# SimpleSwitchPirLightCO2.net
KiCad netlist of a schematic drawn in EAGLE
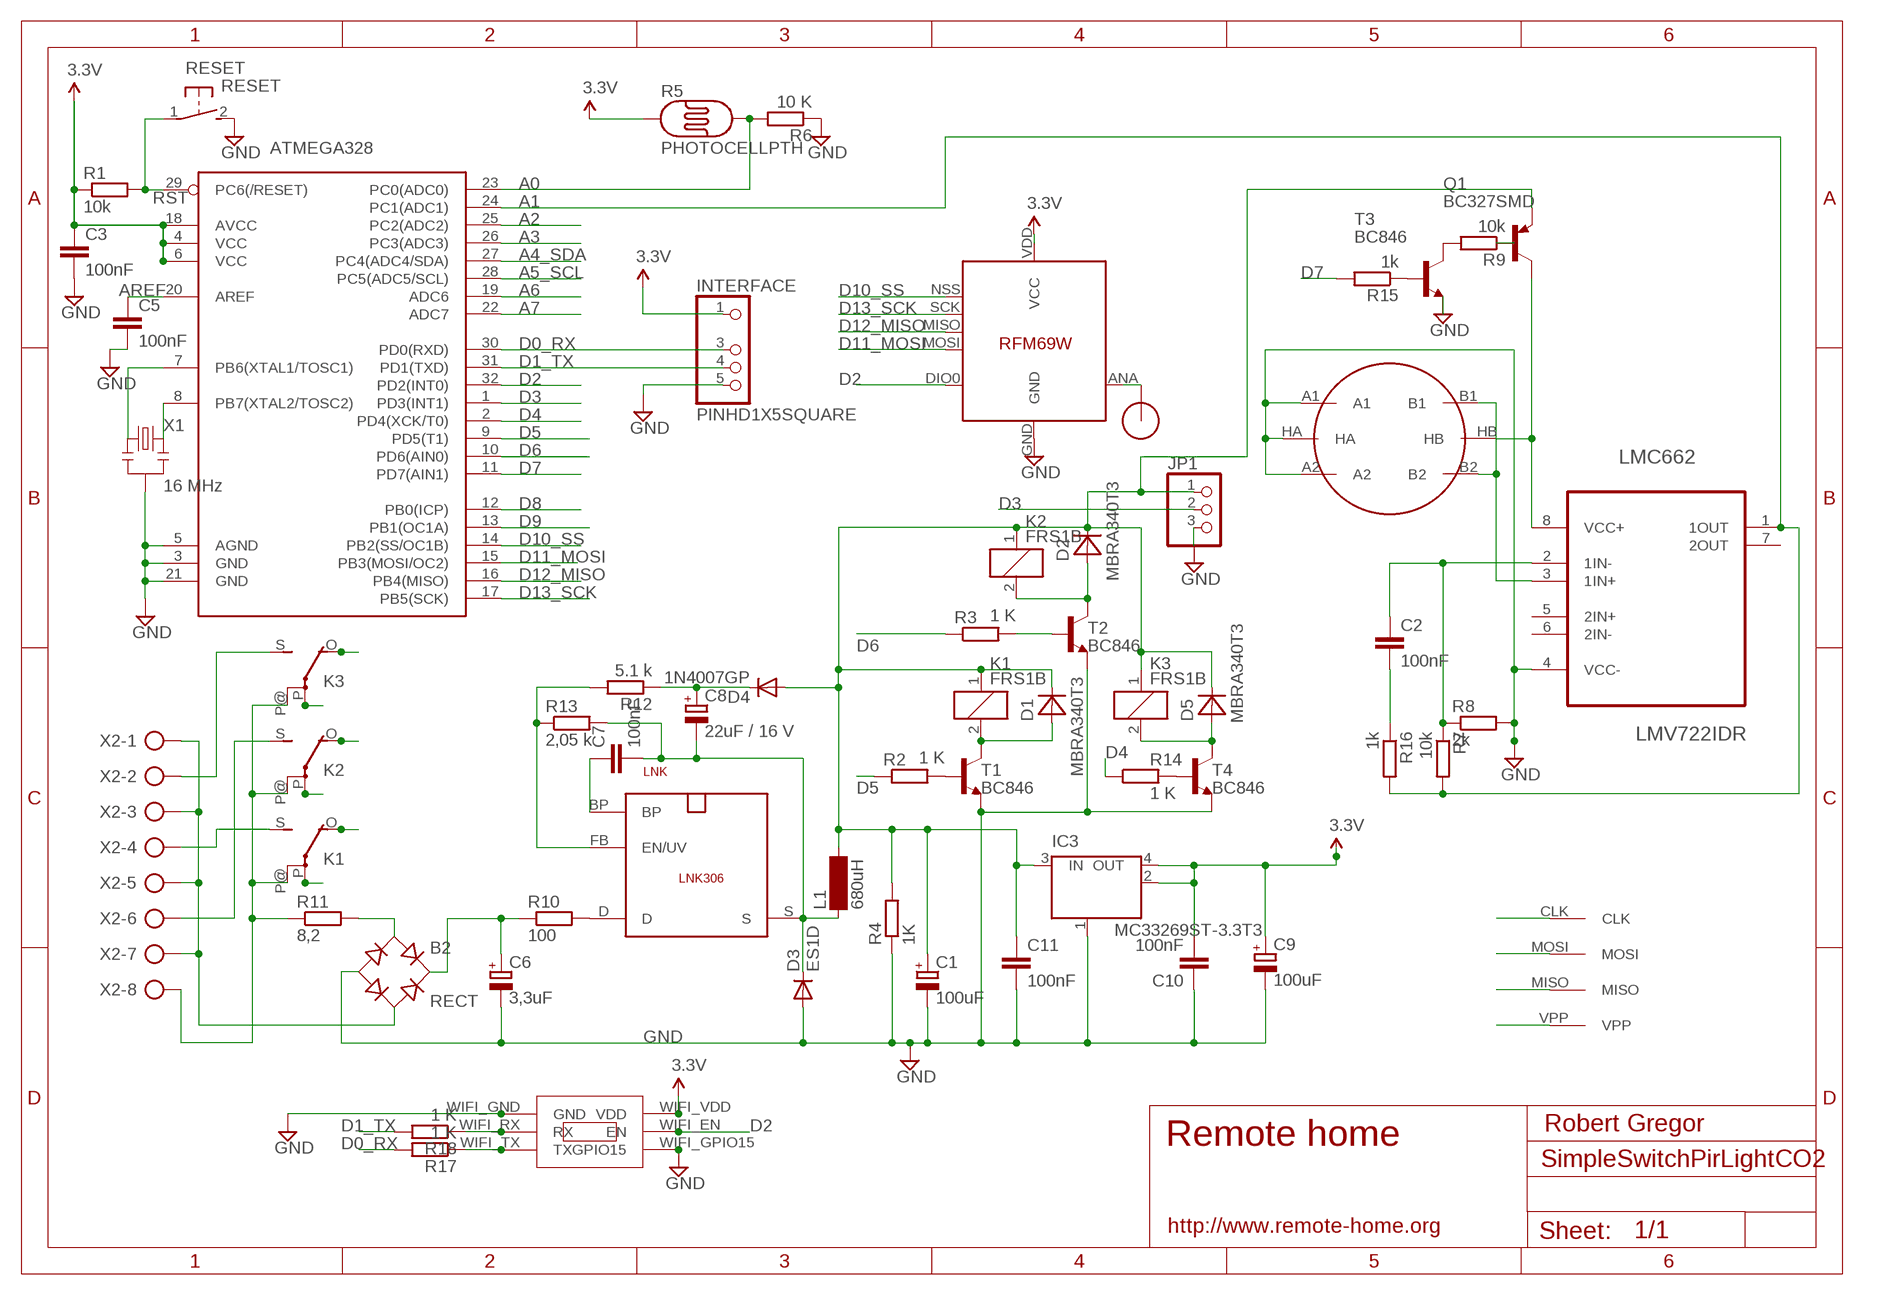
[diagram p0: schematic, sheet 1]

(export (version "E")
  (design (tool "Eeschema 10.0.6"))
  (components
    (comp (ref "ATMEGA328")
      (value "ATMega-328")
      (footprint "eagle-import:TQFP32-08")
      (libsource (lib "eagle-import") (part "ATMEGA168/328TQFP32"))
    )
    (comp (ref "B2")
      (value "RECT")
      (footprint "eagle-import:TO-269AA")
      (libsource (lib "eagle-import") (part "RECTIFIER-S40"))
    )
    (comp (ref "C1")
      (value "100uF")
      (footprint "eagle-import:SMC_B")
      (libsource (lib "eagle-import") (part "CPOL-EUSMCB"))
    )
    (comp (ref "C2")
      (value "100nF")
      (footprint "eagle-import:C2012")
      (libsource (lib "eagle-import") (part "C-EUC2012"))
    )
    (comp (ref "C3")
      (value "100nF")
      (footprint "eagle-import:C2012")
      (libsource (lib "eagle-import") (part "C-EUC2012"))
    )
    (comp (ref "C5")
      (value "100nF")
      (footprint "eagle-import:C2012")
      (libsource (lib "eagle-import") (part "C-EUC2012"))
    )
    (comp (ref "C6")
      (value "3,3uF")
      (footprint "eagle-import:E5-10,5")
      (libsource (lib "eagle-import") (part "CPOL-EUE5-10.5"))
    )
    (comp (ref "C7")
      (value "100nF")
      (footprint "eagle-import:C2012")
      (libsource (lib "eagle-import") (part "C-EUC2012"))
    )
    (comp (ref "C8")
      (value "22uF / 16 V")
      (footprint "eagle-import:SMC_C")
      (libsource (lib "eagle-import") (part "CPOL-EUSMCC"))
    )
    (comp (ref "C9")
      (value "100uF")
      (footprint "eagle-import:SMC_B")
      (libsource (lib "eagle-import") (part "CPOL-EUSMCB"))
    )
    (comp (ref "C10")
      (value "100nF")
      (footprint "eagle-import:C2012")
      (libsource (lib "eagle-import") (part "C-EUC2012"))
    )
    (comp (ref "C11")
      (value "100nF")
      (footprint "eagle-import:C2012")
      (libsource (lib "eagle-import") (part "C-EUC2012"))
    )
    (comp (ref "D1")
      (value "MBRA340T3")
      (footprint "eagle-import:SMA")
      (libsource (lib "eagle-import") (part "MBRA340T3"))
    )
    (comp (ref "D2")
      (value "MBRA340T3")
      (footprint "eagle-import:SMA")
      (libsource (lib "eagle-import") (part "MBRA340T3"))
    )
    (comp (ref "D3")
      (value "ES1D")
      (footprint "eagle-import:DO214AC")
      (libsource (lib "eagle-import") (part "DIODE-DO214AC"))
    )
    (comp (ref "D4")
      (value "1N4007GP")
      (footprint "eagle-import:DO214AA")
      (libsource (lib "eagle-import") (part "DIODE-DO214AA"))
    )
    (comp (ref "D5")
      (value "MBRA340T3")
      (footprint "eagle-import:SMA")
      (libsource (lib "eagle-import") (part "MBRA340T3"))
    )
    (comp (ref "IC3")
      (value "MC33269ST-3.3T3")
      (footprint "eagle-import:SOT223")
      (libsource (lib "eagle-import") (part "MC33269ST-3.3T3"))
    )
    (comp (ref "INTERFACE")
      (value "PINHD1X5SQUARE")
      (footprint "eagle-import:PINHD1X05-SQUARE")
      (libsource (lib "eagle-import") (part "PINHD1X5SQUARE"))
    )
    (comp (ref "JP1")
      (value "PINHD-1X03_2.54-S")
      (footprint "eagle-import:1X03-S")
      (libsource (lib "eagle-import") (part "PINHD-1X03_2.54-S"))
    )
    (comp (ref "K1")
      (value "FRS1B")
      (footprint "eagle-import:FRS1B")
      (libsource (lib "eagle-import") (part "FRS1B"))
    )
    (comp (ref "K2")
      (value "FRS1B")
      (footprint "eagle-import:FRS1B")
      (libsource (lib "eagle-import") (part "FRS1B"))
    )
    (comp (ref "K3")
      (value "FRS1B")
      (footprint "eagle-import:FRS1B")
      (libsource (lib "eagle-import") (part "FRS1B"))
    )
    (comp (ref "L1")
      (value "680uH")
      (footprint "eagle-import:BS11")
      (libsource (lib "eagle-import") (part "BS11"))
    )
    (comp (ref "LMC662")
      (value "LMV722IDR")
      (footprint "eagle-import:SOIC127P600X175-8N")
      (libsource (lib "eagle-import") (part "LMV722IDR"))
    )
    (comp (ref "LNK")
      (value "LNK306")
      (footprint "eagle-import:SO-8C")
      (libsource (lib "eagle-import") (part "SO-8C"))
    )
    (comp (ref "Q1")
      (value "BC327SMD")
      (footprint "eagle-import:SOT23-BEC")
      (libsource (lib "eagle-import") (part "BC327SMD"))
    )
    (comp (ref "R1")
      (value "10k")
      (footprint "eagle-import:R2012")
      (libsource (lib "eagle-import") (part "R-EU_R2012"))
    )
    (comp (ref "R2")
      (value "1 K")
      (footprint "eagle-import:M2012")
      (libsource (lib "eagle-import") (part "R-EU_M2012"))
    )
    (comp (ref "R3")
      (value "1 K")
      (footprint "eagle-import:M2012")
      (libsource (lib "eagle-import") (part "R-EU_M2012"))
    )
    (comp (ref "R4")
      (value "1K")
      (footprint "eagle-import:M2012")
      (libsource (lib "eagle-import") (part "R-EU_M2012"))
    )
    (comp (ref "R5")
      (value "PHOTOCELLPTH")
      (footprint "eagle-import:PHOTOCELL")
      (libsource (lib "eagle-import") (part "PHOTOCELLPTH"))
    )
    (comp (ref "R6")
      (value "10 K")
      (footprint "eagle-import:M2012")
      (libsource (lib "eagle-import") (part "R-EU_M2012"))
    )
    (comp (ref "R7")
      (value "10k")
      (footprint "eagle-import:R2012")
      (libsource (lib "eagle-import") (part "R-EU_R2012"))
    )
    (comp (ref "R8")
      (value "2k")
      (footprint "eagle-import:R2012")
      (libsource (lib "eagle-import") (part "R-EU_R2012"))
    )
    (comp (ref "R9")
      (value "10k")
      (footprint "eagle-import:R2012")
      (libsource (lib "eagle-import") (part "R-EU_R2012"))
    )
    (comp (ref "R10")
      (value "100")
      (footprint "eagle-import:R2512W")
      (libsource (lib "eagle-import") (part "R-EU_R2512W"))
    )
    (comp (ref "R11")
      (value "8,2")
      (footprint "eagle-import:0411_12")
      (libsource (lib "eagle-import") (part "R-EU_0411/12"))
    )
    (comp (ref "R12")
      (value "5.1 k")
      (footprint "eagle-import:M2012")
      (libsource (lib "eagle-import") (part "R-EU_M2012"))
    )
    (comp (ref "R13")
      (value "2,05 k")
      (footprint "eagle-import:M2012")
      (libsource (lib "eagle-import") (part "R-EU_M2012"))
    )
    (comp (ref "R14")
      (value "1 K")
      (footprint "eagle-import:M2012")
      (libsource (lib "eagle-import") (part "R-EU_M2012"))
    )
    (comp (ref "R15")
      (value "1k")
      (footprint "eagle-import:R2012")
      (libsource (lib "eagle-import") (part "R-EU_R2012"))
    )
    (comp (ref "R16")
      (value "1k")
      (footprint "eagle-import:R2012")
      (libsource (lib "eagle-import") (part "R-EU_R2012"))
    )
    (comp (ref "R17")
      (value "1 K")
      (footprint "eagle-import:M2012")
      (libsource (lib "eagle-import") (part "R-EU_M2012"))
    )
    (comp (ref "R18")
      (value "1 K")
      (footprint "eagle-import:M2012")
      (libsource (lib "eagle-import") (part "R-EU_M2012"))
    )
    (comp (ref "RESET")
      (value "RESET")
      (footprint "eagle-import:DTSM-3")
      (libsource (lib "eagle-import") (part "DTSM-3"))
    )
    (comp (ref "RFM69")
      (value "RFM69W")
      (footprint "eagle-import:RFM69W")
      (libsource (lib "eagle-import") (part "RFM69W"))
    )
    (comp (ref "T1")
      (value "BC846")
      (footprint "eagle-import:SOT23")
      (libsource (lib "eagle-import") (part "BC846"))
    )
    (comp (ref "T2")
      (value "BC846")
      (footprint "eagle-import:SOT23")
      (libsource (lib "eagle-import") (part "BC846"))
    )
    (comp (ref "T3")
      (value "BC846")
      (footprint "eagle-import:SOT23")
      (libsource (lib "eagle-import") (part "BC846"))
    )
    (comp (ref "T4")
      (value "BC846")
      (footprint "eagle-import:SOT23")
      (libsource (lib "eagle-import") (part "BC846"))
    )
    (comp (ref "U$1")
      (value "RFM12B_ANTENNA")
      (footprint "eagle-import:RFM12B-ANTENNA")
      (libsource (lib "eagle-import") (part "RFM12B_ANTENNA"))
    )
    (comp (ref "U$2")
      (value "AVRHEADERDIP")
      (footprint "eagle-import:AVRHEADER")
      (libsource (lib "eagle-import") (part "AVRHEADERDIP"))
    )
    (comp (ref "U$4")
      (value "METHANE_SENSOR")
      (footprint "eagle-import:MQ-3")
      (libsource (lib "eagle-import") (part "METHANE_SENSOR"))
    )
    (comp (ref "U$5")
      (value "ESP03")
      (footprint "eagle-import:ESP03")
      (libsource (lib "eagle-import") (part "ESP03"))
    )
    (comp (ref "X1")
      (value "16 MHz")
      (footprint "eagle-import:RESONATOR-SMD")
      (libsource (lib "eagle-import") (part "RESONATORSMD"))
    )
    (comp (ref "X2")
      (value "AK500/8")
      (footprint "eagle-import:AK500_8")
      (libsource (lib "eagle-import") (part "AK500/8"))
    )
  )
  (nets
    (net (code "1") (name "/A0") (class "Default")
      (node (ref "ATMEGA328") (pin "23") (pinfunction "PC0(ADC0)_23") (pintype "bidirectional"))
      (node (ref "R5") (pin "2") (pinfunction "P$2_2") (pintype "bidirectional"))
      (node (ref "R6") (pin "2") (pinfunction "2_2") (pintype "passive"))
    )
    (net (code "2") (name "/A1") (class "Default")
      (node (ref "ATMEGA328") (pin "24") (pinfunction "PC1(ADC1)_24") (pintype "bidirectional"))
      (node (ref "LMC662") (pin "1") (pinfunction "1OUT_1") (pintype "output"))
      (node (ref "R16") (pin "2") (pinfunction "2_2") (pintype "passive"))
      (node (ref "R7") (pin "2") (pinfunction "2_2") (pintype "passive"))
    )
    (net (code "3") (name "/A2") (class "Default")
      (node (ref "ATMEGA328") (pin "25") (pinfunction "PC2(ADC2)_25") (pintype "bidirectional"))
    )
    (net (code "4") (name "/A3") (class "Default")
      (node (ref "ATMEGA328") (pin "26") (pinfunction "PC3(ADC3)_26") (pintype "bidirectional"))
    )
    (net (code "5") (name "/A4_SDA") (class "Default")
      (node (ref "ATMEGA328") (pin "27") (pinfunction "PC4(ADC4/SDA)_27") (pintype "bidirectional"))
    )
    (net (code "6") (name "/A5_SCL") (class "Default")
      (node (ref "ATMEGA328") (pin "28") (pinfunction "PC5(ADC5/SCL)_28") (pintype "bidirectional"))
    )
    (net (code "7") (name "/A6") (class "Default")
      (node (ref "ATMEGA328") (pin "19") (pinfunction "ADC6_19") (pintype "bidirectional"))
    )
    (net (code "8") (name "/A7") (class "Default")
      (node (ref "ATMEGA328") (pin "22") (pinfunction "ADC7_22") (pintype "bidirectional"))
    )
    (net (code "9") (name "/AREF") (class "Default")
      (node (ref "ATMEGA328") (pin "20") (pinfunction "AREF_20") (pintype "bidirectional"))
      (node (ref "C5") (pin "1") (pinfunction "1_1") (pintype "passive"))
    )
    (net (code "10") (name "/D0_RX") (class "Default")
      (node (ref "ATMEGA328") (pin "30") (pinfunction "PD0(RXD)_30") (pintype "bidirectional"))
      (node (ref "INTERFACE") (pin "3") (pinfunction "3_3") (pintype "passive"))
      (node (ref "R17") (pin "2") (pinfunction "2_2") (pintype "passive"))
    )
    (net (code "11") (name "/D1_TX") (class "Default")
      (node (ref "ATMEGA328") (pin "31") (pinfunction "PD1(TXD)_31") (pintype "bidirectional"))
      (node (ref "INTERFACE") (pin "4") (pinfunction "4_4") (pintype "passive"))
      (node (ref "R18") (pin "2") (pinfunction "2_2") (pintype "passive"))
    )
    (net (code "12") (name "/D2") (class "Default")
      (node (ref "ATMEGA328") (pin "32") (pinfunction "PD2(INT0)_32") (pintype "bidirectional"))
      (node (ref "RFM69") (pin "DIO0") (pinfunction "DIO0_DIO0") (pintype "open_collector"))
      (node (ref "U$5") (pin "WIFI_EN") (pinfunction "EN_WIFI_EN") (pintype "input"))
    )
    (net (code "13") (name "/D3") (class "Default")
      (node (ref "ATMEGA328") (pin "1") (pinfunction "PD3(INT1)_1") (pintype "bidirectional"))
      (node (ref "JP1") (pin "2") (pinfunction "2_2") (pintype "passive"))
    )
    (net (code "14") (name "/D4") (class "Default")
      (node (ref "ATMEGA328") (pin "2") (pinfunction "PD4(XCK/T0)_2") (pintype "bidirectional"))
      (node (ref "R14") (pin "1") (pinfunction "1_1") (pintype "passive"))
    )
    (net (code "15") (name "/D5") (class "Default")
      (node (ref "ATMEGA328") (pin "9") (pinfunction "PD5(T1)_9") (pintype "bidirectional"))
      (node (ref "R2") (pin "1") (pinfunction "1_1") (pintype "passive"))
    )
    (net (code "16") (name "/D6") (class "Default")
      (node (ref "ATMEGA328") (pin "10") (pinfunction "PD6(AIN0)_10") (pintype "bidirectional"))
      (node (ref "R3") (pin "1") (pinfunction "1_1") (pintype "passive"))
    )
    (net (code "17") (name "/D7") (class "Default")
      (node (ref "ATMEGA328") (pin "11") (pinfunction "PD7(AIN1)_11") (pintype "bidirectional"))
      (node (ref "R15") (pin "2") (pinfunction "2_2") (pintype "passive"))
    )
    (net (code "18") (name "/D8") (class "Default")
      (node (ref "ATMEGA328") (pin "12") (pinfunction "PB0(ICP)_12") (pintype "bidirectional"))
    )
    (net (code "19") (name "/D9") (class "Default")
      (node (ref "ATMEGA328") (pin "13") (pinfunction "PB1(OC1A)_13") (pintype "bidirectional"))
    )
    (net (code "20") (name "/D10_SS") (class "Default")
      (node (ref "ATMEGA328") (pin "14") (pinfunction "PB2(SS/OC1B)_14") (pintype "bidirectional"))
      (node (ref "RFM69") (pin "NSS") (pinfunction "SEL_NSS") (pintype "input"))
    )
    (net (code "21") (name "/D11_MOSI") (class "Default")
      (node (ref "ATMEGA328") (pin "15") (pinfunction "PB3(MOSI/OC2)_15") (pintype "bidirectional"))
      (node (ref "RFM69") (pin "MOSI") (pinfunction "MOSI_MOSI") (pintype "output"))
      (node (ref "U$2") (pin "MOSI") (pinfunction "MOSI_MOSI") (pintype "bidirectional"))
    )
    (net (code "22") (name "/D12_MISO") (class "Default")
      (node (ref "ATMEGA328") (pin "16") (pinfunction "PB4(MISO)_16") (pintype "bidirectional"))
      (node (ref "RFM69") (pin "MISO") (pinfunction "MISO_MISO") (pintype "input"))
      (node (ref "U$2") (pin "MISO") (pinfunction "MISO_MISO") (pintype "bidirectional"))
    )
    (net (code "23") (name "/D13_SCK") (class "Default")
      (node (ref "ATMEGA328") (pin "17") (pinfunction "PB5(SCK)_17") (pintype "bidirectional"))
      (node (ref "RFM69") (pin "SCK") (pinfunction "SCK_SCK") (pintype "input"))
      (node (ref "U$2") (pin "CLK") (pinfunction "CLK_CLK") (pintype "bidirectional"))
    )
    (net (code "24") (name "/RST") (class "Default")
      (node (ref "ATMEGA328") (pin "29") (pinfunction "PC6(/RESET)_29") (pintype "bidirectional"))
      (node (ref "R1") (pin "2") (pinfunction "2_2") (pintype "passive"))
      (node (ref "RESET") (pin "1") (pinfunction "1_1") (pintype "passive"))
      (node (ref "U$2") (pin "VPP") (pinfunction "VPP_VPP") (pintype "bidirectional"))
    )
    (net (code "25") (name "3.3V") (class "Default")
      (node (ref "ATMEGA328") (pin "18") (pinfunction "AVCC_18") (pintype "bidirectional"))
      (node (ref "ATMEGA328") (pin "4") (pinfunction "VCC_4") (pintype "bidirectional"))
      (node (ref "ATMEGA328") (pin "6") (pinfunction "VCC_6") (pintype "bidirectional"))
      (node (ref "C10") (pin "2") (pinfunction "2_2") (pintype "passive"))
      (node (ref "C3") (pin "1") (pinfunction "1_1") (pintype "passive"))
      (node (ref "C9") (pin "+") (pinfunction "+_+") (pintype "passive"))
      (node (ref "IC3") (pin "2") (pinfunction "OUT_2") (pintype "passive"))
      (node (ref "IC3") (pin "4") (pinfunction "OUT_4") (pintype "passive"))
      (node (ref "INTERFACE") (pin "1") (pinfunction "1_1") (pintype "passive"))
      (node (ref "R1") (pin "1") (pinfunction "1_1") (pintype "passive"))
      (node (ref "R5") (pin "1") (pinfunction "P$1_1") (pintype "bidirectional"))
      (node (ref "RFM69") (pin "VDD") (pinfunction "VCC_VDD") (pintype "power_in"))
      (node (ref "U$5") (pin "WIFI_VDD") (pinfunction "VDD_WIFI_VDD") (pintype "power_in"))
    )
    (net (code "26") (name "GND") (class "Default")
      (node (ref "ATMEGA328") (pin "21") (pinfunction "GND_21") (pintype "bidirectional"))
      (node (ref "ATMEGA328") (pin "3") (pinfunction "GND_3") (pintype "bidirectional"))
      (node (ref "ATMEGA328") (pin "5") (pinfunction "AGND_5") (pintype "bidirectional"))
      (node (ref "B2") (pin "-") (pinfunction "-_-") (pintype "passive"))
      (node (ref "C1") (pin "-") (pinfunction "-_-") (pintype "passive"))
      (node (ref "C10") (pin "1") (pinfunction "1_1") (pintype "passive"))
      (node (ref "C11") (pin "2") (pinfunction "2_2") (pintype "passive"))
      (node (ref "C3") (pin "2") (pinfunction "2_2") (pintype "passive"))
      (node (ref "C5") (pin "2") (pinfunction "2_2") (pintype "passive"))
      (node (ref "C6") (pin "-") (pinfunction "-_-") (pintype "passive"))
      (node (ref "C9") (pin "-") (pinfunction "-_-") (pintype "passive"))
      (node (ref "D3") (pin "A") (pinfunction "A_A") (pintype "passive"))
      (node (ref "IC3") (pin "1") (pinfunction "GND/ADJ_1") (pintype "input"))
      (node (ref "INTERFACE") (pin "5") (pinfunction "5_5") (pintype "passive"))
      (node (ref "JP1") (pin "3") (pinfunction "3_3") (pintype "passive"))
      (node (ref "LMC662") (pin "4") (pinfunction "VCC-_4") (pintype "power_in"))
      (node (ref "R4") (pin "1") (pinfunction "1_1") (pintype "passive"))
      (node (ref "R6") (pin "1") (pinfunction "1_1") (pintype "passive"))
      (node (ref "R8") (pin "2") (pinfunction "2_2") (pintype "passive"))
      (node (ref "RESET") (pin "2") (pinfunction "2_2") (pintype "passive"))
      (node (ref "RFM69") (pin "GND") (pinfunction "GND_GND") (pintype "power_in"))
      (node (ref "T1") (pin "2") (pinfunction "E_2") (pintype "passive"))
      (node (ref "T2") (pin "2") (pinfunction "E_2") (pintype "passive"))
      (node (ref "T3") (pin "2") (pinfunction "E_2") (pintype "passive"))
      (node (ref "T4") (pin "2") (pinfunction "E_2") (pintype "passive"))
      (node (ref "U$4") (pin "A1") (pinfunction "A1_A1") (pintype "bidirectional"))
      (node (ref "U$4") (pin "A2") (pinfunction "A2_A2") (pintype "bidirectional"))
      (node (ref "U$4") (pin "HA") (pinfunction "HA_HA") (pintype "bidirectional"))
      (node (ref "U$5") (pin "WIFI_GND") (pinfunction "GND_WIFI_GND") (pintype "power_in"))
      (node (ref "U$5") (pin "WIFI_GPIO15") (pinfunction "GPIO15_WIFI_GPIO15") (pintype "input"))
      (node (ref "X1") (pin "2") (pinfunction "2_2") (pintype "passive"))
    )
    (net (code "27") (name "Net-(ATMEGA328-PB6(XTAL1{slash}TOSC1))") (class "Default")
      (node (ref "ATMEGA328") (pin "7") (pinfunction "PB6(XTAL1/TOSC1)_7") (pintype "bidirectional"))
      (node (ref "X1") (pin "1") (pinfunction "1_1") (pintype "passive"))
    )
    (net (code "28") (name "Net-(ATMEGA328-PB7(XTAL2{slash}TOSC2))") (class "Default")
      (node (ref "ATMEGA328") (pin "8") (pinfunction "PB7(XTAL2/TOSC2)_8") (pintype "bidirectional"))
      (node (ref "X1") (pin "3") (pinfunction "3_3") (pintype "passive"))
    )
    (net (code "29") (name "Net-(B2-Pad+)") (class "Default")
      (node (ref "B2") (pin "+") (pinfunction "+_+") (pintype "passive"))
      (node (ref "C6") (pin "+") (pinfunction "+_+") (pintype "passive"))
      (node (ref "R10") (pin "1") (pinfunction "1_1") (pintype "passive"))
    )
    (net (code "30") (name "Net-(B2-PadAC1)") (class "Default")
      (node (ref "B2") (pin "AC1") (pinfunction "AC1_AC1") (pintype "passive"))
      (node (ref "R11") (pin "2") (pinfunction "2_2") (pintype "passive"))
    )
    (net (code "31") (name "Net-(C2-Pad2)") (class "Default")
      (node (ref "C2") (pin "2") (pinfunction "2_2") (pintype "passive"))
      (node (ref "R16") (pin "1") (pinfunction "1_1") (pintype "passive"))
    )
    (net (code "32") (name "Net-(C7-Pad1)") (class "Default")
      (node (ref "C7") (pin "1") (pinfunction "1_1") (pintype "passive"))
      (node (ref "LNK") (pin "BP") (pinfunction "BP_BP") (pintype "passive"))
    )
    (net (code "33") (name "Net-(C7-Pad2)") (class "Default")
      (node (ref "C7") (pin "2") (pinfunction "2_2") (pintype "passive"))
      (node (ref "C8") (pin "-") (pinfunction "-_-") (pintype "passive"))
      (node (ref "D3") (pin "C") (pinfunction "C_C") (pintype "passive"))
      (node (ref "L1") (pin "1") (pinfunction "1_1") (pintype "passive"))
      (node (ref "LNK") (pin "S") (pinfunction "S_S") (pintype "power_in"))
      (node (ref "R13") (pin "2") (pinfunction "2_2") (pintype "passive"))
    )
    (net (code "34") (name "Net-(C8-Pad+)") (class "Default")
      (node (ref "C8") (pin "+") (pinfunction "+_+") (pintype "passive"))
      (node (ref "D4") (pin "C") (pinfunction "C_C") (pintype "passive"))
      (node (ref "R12") (pin "1") (pinfunction "1_1") (pintype "passive"))
    )
    (net (code "35") (name "Net-(IC3-IN)") (class "Default")
      (node (ref "C1") (pin "+") (pinfunction "+_+") (pintype "passive"))
      (node (ref "C11") (pin "1") (pinfunction "1_1") (pintype "passive"))
      (node (ref "D1") (pin "C") (pinfunction "C_C") (pintype "passive"))
      (node (ref "D2") (pin "C") (pinfunction "C_C") (pintype "passive"))
      (node (ref "D4") (pin "A") (pinfunction "A_A") (pintype "passive"))
      (node (ref "D5") (pin "C") (pinfunction "C_C") (pintype "passive"))
      (node (ref "IC3") (pin "3") (pinfunction "IN_3") (pintype "input"))
      (node (ref "JP1") (pin "1") (pinfunction "1_1") (pintype "passive"))
      (node (ref "K1") (pin "1") (pinfunction "1_1") (pintype "passive"))
      (node (ref "K2") (pin "1") (pinfunction "1_1") (pintype "passive"))
      (node (ref "K3") (pin "1") (pinfunction "1_1") (pintype "passive"))
      (node (ref "L1") (pin "2") (pinfunction "2_2") (pintype "passive"))
      (node (ref "Q1") (pin "E") (pinfunction "E_E") (pintype "passive"))
      (node (ref "R4") (pin "2") (pinfunction "2_2") (pintype "passive"))
    )
    (net (code "36") (name "Net-(LMC662-1IN+)") (class "Default")
      (node (ref "LMC662") (pin "3") (pinfunction "1IN+_3") (pintype "input"))
      (node (ref "U$4") (pin "B1") (pinfunction "B1_B1") (pintype "bidirectional"))
      (node (ref "U$4") (pin "B2") (pinfunction "B2_B2") (pintype "bidirectional"))
    )
    (net (code "37") (name "Net-(LMC662-1IN-)") (class "Default")
      (node (ref "C2") (pin "1") (pinfunction "1_1") (pintype "passive"))
      (node (ref "LMC662") (pin "2") (pinfunction "1IN-_2") (pintype "input"))
      (node (ref "R7") (pin "1") (pinfunction "1_1") (pintype "passive"))
      (node (ref "R8") (pin "1") (pinfunction "1_1") (pintype "passive"))
    )
    (net (code "38") (name "Net-(LMC662-VCC+)") (class "Default")
      (node (ref "LMC662") (pin "8") (pinfunction "VCC+_8") (pintype "power_in"))
      (node (ref "Q1") (pin "C") (pinfunction "C_C") (pintype "passive"))
      (node (ref "U$4") (pin "HB") (pinfunction "HB_HB") (pintype "bidirectional"))
    )
    (net (code "39") (name "Net-(LNK-EN{slash}UV)") (class "Default")
      (node (ref "LNK") (pin "FB") (pinfunction "EN/UV_FB") (pintype "input"))
      (node (ref "R12") (pin "2") (pinfunction "2_2") (pintype "passive"))
      (node (ref "R13") (pin "1") (pinfunction "1_1") (pintype "passive"))
    )
    (net (code "40") (name "Net-(LNK-PadD)") (class "Default")
      (node (ref "LNK") (pin "D") (pinfunction "D_D") (pintype "open_collector"))
      (node (ref "R10") (pin "2") (pinfunction "2_2") (pintype "passive"))
    )
    (net (code "41") (name "Net-(Q1-PadB)") (class "Default")
      (node (ref "Q1") (pin "B") (pinfunction "B_B") (pintype "passive"))
      (node (ref "R9") (pin "1") (pinfunction "1_1") (pintype "passive"))
    )
    (net (code "42") (name "Net-(RFM69-ANT)") (class "Default")
      (node (ref "RFM69") (pin "ANA") (pinfunction "ANT_ANA") (pintype "passive"))
      (node (ref "U$1") (pin "P$1") (pinfunction "1_P$1") (pintype "bidirectional"))
    )
    (net (code "43") (name "Net-(T1-B)") (class "Default")
      (node (ref "R2") (pin "2") (pinfunction "2_2") (pintype "passive"))
      (node (ref "T1") (pin "1") (pinfunction "B_1") (pintype "passive"))
    )
    (net (code "44") (name "Net-(T1-C)") (class "Default")
      (node (ref "D1") (pin "A") (pinfunction "A_A") (pintype "passive"))
      (node (ref "K1") (pin "2") (pinfunction "2_2") (pintype "passive"))
      (node (ref "T1") (pin "3") (pinfunction "C_3") (pintype "passive"))
    )
    (net (code "45") (name "Net-(T2-B)") (class "Default")
      (node (ref "R3") (pin "2") (pinfunction "2_2") (pintype "passive"))
      (node (ref "T2") (pin "1") (pinfunction "B_1") (pintype "passive"))
    )
    (net (code "46") (name "Net-(T2-C)") (class "Default")
      (node (ref "D2") (pin "A") (pinfunction "A_A") (pintype "passive"))
      (node (ref "K2") (pin "2") (pinfunction "2_2") (pintype "passive"))
      (node (ref "T2") (pin "3") (pinfunction "C_3") (pintype "passive"))
    )
    (net (code "47") (name "Net-(T3-B)") (class "Default")
      (node (ref "R15") (pin "1") (pinfunction "1_1") (pintype "passive"))
      (node (ref "T3") (pin "1") (pinfunction "B_1") (pintype "passive"))
    )
    (net (code "48") (name "Net-(T3-C)") (class "Default")
      (node (ref "R9") (pin "2") (pinfunction "2_2") (pintype "passive"))
      (node (ref "T3") (pin "3") (pinfunction "C_3") (pintype "passive"))
    )
    (net (code "49") (name "Net-(T4-B)") (class "Default")
      (node (ref "R14") (pin "2") (pinfunction "2_2") (pintype "passive"))
      (node (ref "T4") (pin "1") (pinfunction "B_1") (pintype "passive"))
    )
    (net (code "50") (name "Net-(T4-C)") (class "Default")
      (node (ref "D5") (pin "A") (pinfunction "A_A") (pintype "passive"))
      (node (ref "K3") (pin "2") (pinfunction "2_2") (pintype "passive"))
      (node (ref "T4") (pin "3") (pinfunction "C_3") (pintype "passive"))
    )
    (net (code "51") (name "Net-(U$5-RX)") (class "Default")
      (node (ref "R18") (pin "1") (pinfunction "1_1") (pintype "passive"))
      (node (ref "U$5") (pin "WIFI_RX") (pinfunction "RX_WIFI_RX") (pintype "input"))
    )
    (net (code "52") (name "Net-(U$5-TX)") (class "Default")
      (node (ref "R17") (pin "1") (pinfunction "1_1") (pintype "passive"))
      (node (ref "U$5") (pin "WIFI_TX") (pinfunction "TX_WIFI_TX") (pintype "output"))
    )
    (net (code "53") (name "Net-(X2A-KL)") (class "Default")
      (node (ref "B2") (pin "AC2") (pinfunction "AC2_AC2") (pintype "passive"))
      (node (ref "X2") (pin "1") (pinfunction "KL_1") (pintype "passive"))
      (node (ref "X2") (pin "3") (pinfunction "KL_3") (pintype "passive"))
      (node (ref "X2") (pin "5") (pinfunction "KL_5") (pintype "passive"))
      (node (ref "X2") (pin "7") (pinfunction "KL_7") (pintype "passive"))
    )
    (net (code "54") (name "Net-(X2B-KL)") (class "Default")
      (node (ref "K3") (pin "S") (pinfunction "S_S") (pintype "passive"))
      (node (ref "X2") (pin "2") (pinfunction "KL_2") (pintype "passive"))
    )
    (net (code "55") (name "Net-(X2D-KL)") (class "Default")
      (node (ref "K1") (pin "S") (pinfunction "S_S") (pintype "passive"))
      (node (ref "X2") (pin "4") (pinfunction "KL_4") (pintype "passive"))
    )
    (net (code "56") (name "Net-(X2F-KL)") (class "Default")
      (node (ref "K2") (pin "S") (pinfunction "S_S") (pintype "passive"))
      (node (ref "X2") (pin "6") (pinfunction "KL_6") (pintype "passive"))
    )
    (net (code "57") (name "Net-(X2H-KL)") (class "Default")
      (node (ref "K1") (pin "P@") (pinfunction "P_P@") (pintype "passive"))
      (node (ref "K2") (pin "P@") (pinfunction "P_P@") (pintype "passive"))
      (node (ref "K3") (pin "P@") (pinfunction "P_P@") (pintype "passive"))
      (node (ref "R11") (pin "1") (pinfunction "1_1") (pintype "passive"))
      (node (ref "X2") (pin "8") (pinfunction "KL_8") (pintype "passive"))
    )
    (net (code "58") (name "unconnected-(K1-PadO)") (class "Default")
      (node (ref "K1") (pin "O") (pinfunction "O_O") (pintype "passive"))
    )
    (net (code "59") (name "unconnected-(K1-PadP)") (class "Default")
      (node (ref "K1") (pin "P") (pinfunction "P_P") (pintype "passive"))
    )
    (net (code "60") (name "unconnected-(K2-PadO)") (class "Default")
      (node (ref "K2") (pin "O") (pinfunction "O_O") (pintype "passive"))
    )
    (net (code "61") (name "unconnected-(K2-PadP)") (class "Default")
      (node (ref "K2") (pin "P") (pinfunction "P_P") (pintype "passive"))
    )
    (net (code "62") (name "unconnected-(K3-PadO)") (class "Default")
      (node (ref "K3") (pin "O") (pinfunction "O_O") (pintype "passive"))
    )
    (net (code "63") (name "unconnected-(K3-PadP)") (class "Default")
      (node (ref "K3") (pin "P") (pinfunction "P_P") (pintype "passive"))
    )
    (net (code "64") (name "unconnected-(LMC662-2IN+-Pad5)") (class "Default")
      (node (ref "LMC662") (pin "5") (pinfunction "2IN+_5") (pintype "input"))
    )
    (net (code "65") (name "unconnected-(LMC662-2IN--Pad6)") (class "Default")
      (node (ref "LMC662") (pin "6") (pinfunction "2IN-_6") (pintype "input"))
    )
    (net (code "66") (name "unconnected-(LMC662-2OUT-Pad7)") (class "Default")
      (node (ref "LMC662") (pin "7") (pinfunction "2OUT_7") (pintype "output"))
    )
  )
)
